# Hardware_v3.net
KiCad netlist of a schematic drawn in EAGLE
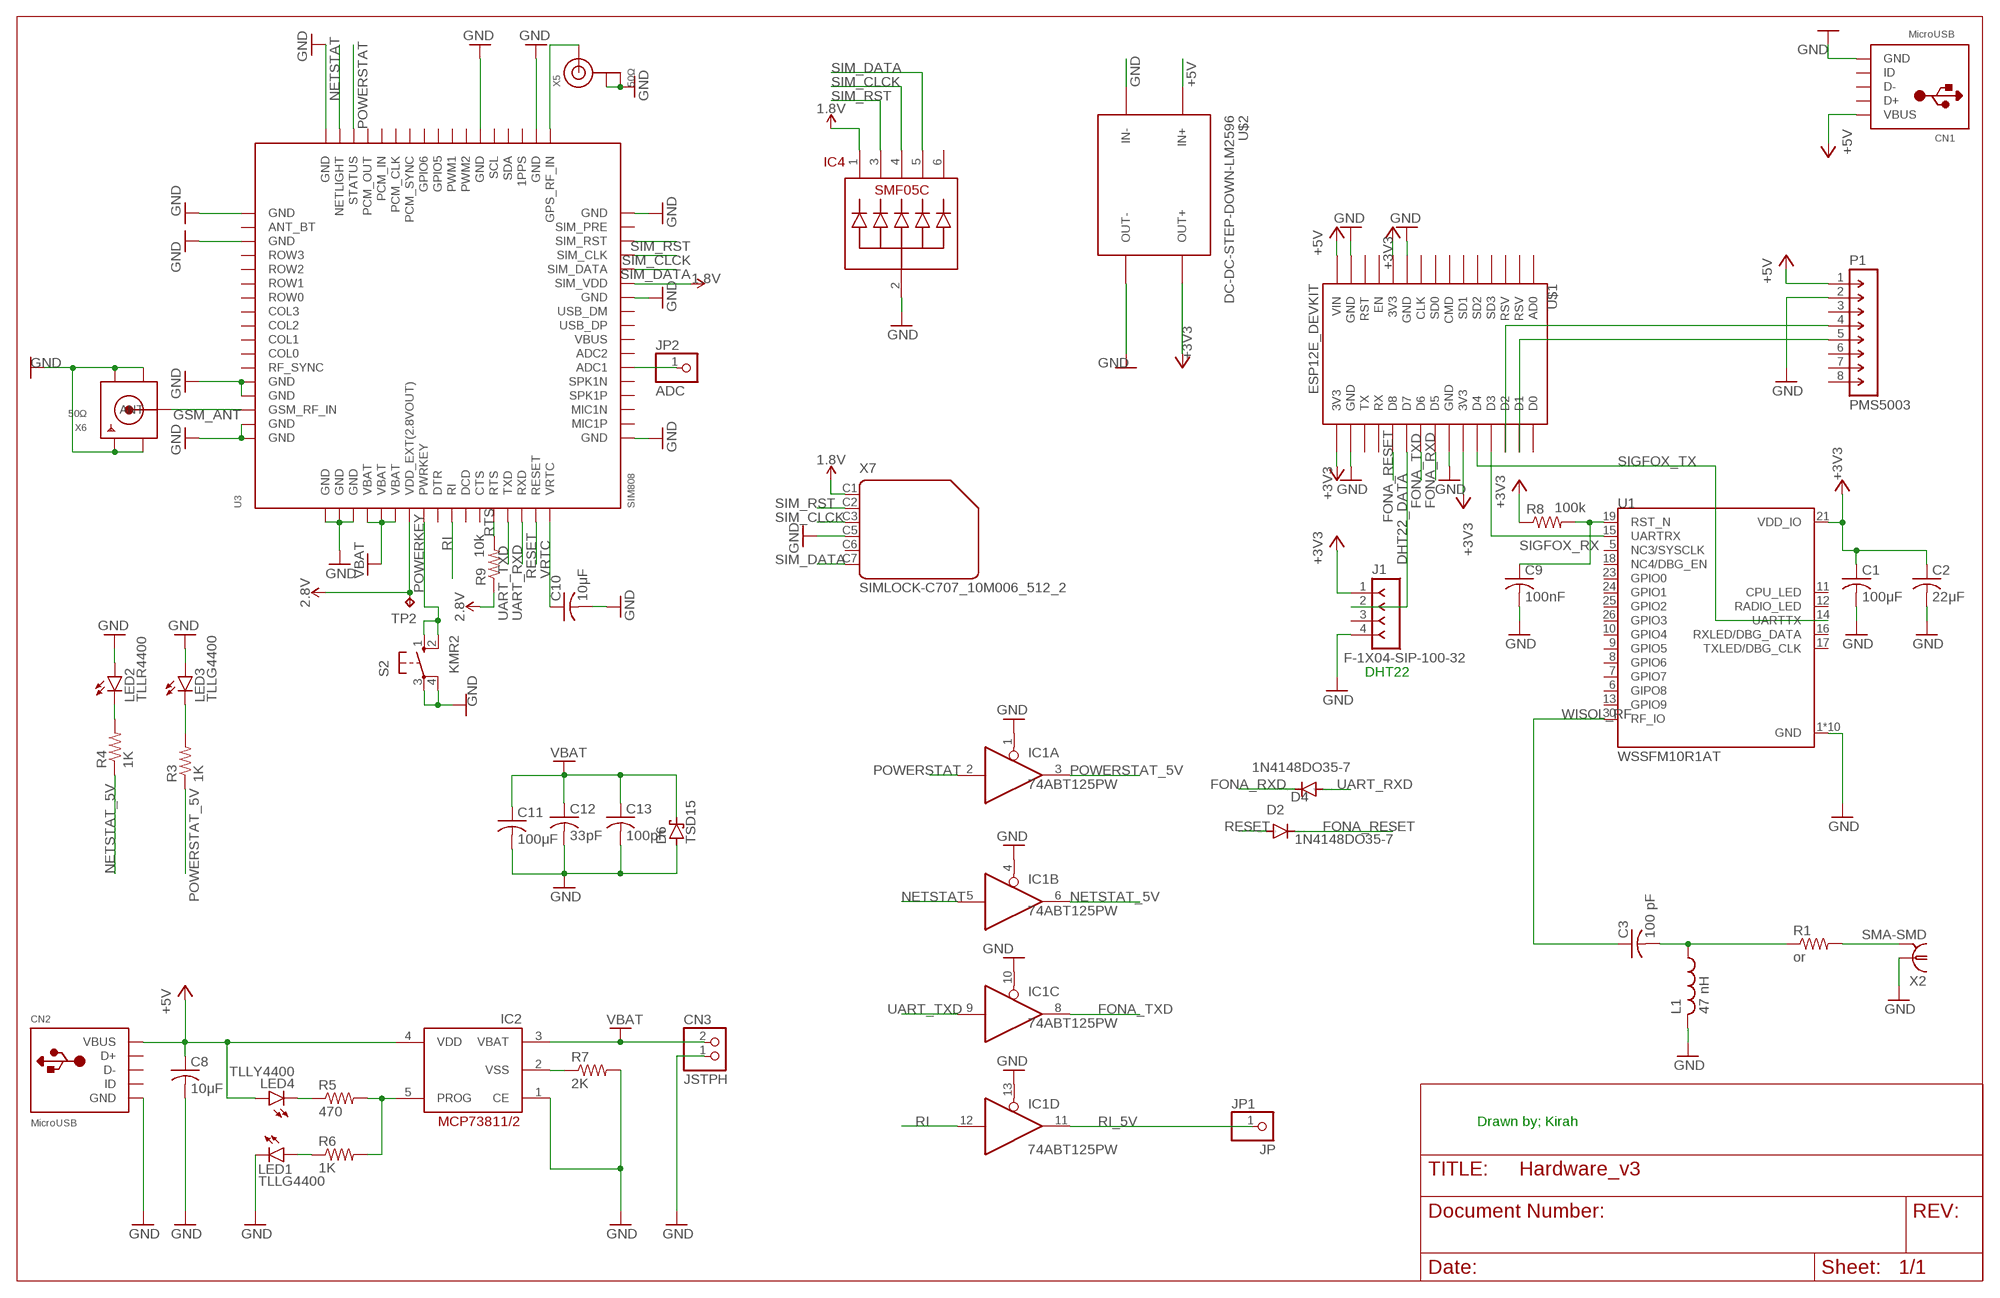
[diagram p0: schematic, sheet 1]

(export (version "E")
  (design (tool "Eeschema 10.0.6"))
  (components
    (comp (ref "C1")
      (value "100μF")
      (footprint "eagle-import:C0201")
      (libsource (lib "eagle-import") (part "C-USC0201"))
    )
    (comp (ref "C2")
      (value "22μF")
      (footprint "eagle-import:C0201")
      (libsource (lib "eagle-import") (part "C-USC0201"))
    )
    (comp (ref "C3")
      (value "100 pF")
      (footprint "eagle-import:C0201")
      (libsource (lib "eagle-import") (part "C-USC0201"))
    )
    (comp (ref "C8")
      (value "10μF")
      (footprint "eagle-import:C025-025X050")
      (libsource (lib "eagle-import") (part "C-US025-025X050"))
    )
    (comp (ref "C9")
      (value "100nF")
      (footprint "eagle-import:C025-025X050")
      (libsource (lib "eagle-import") (part "rcl_C-US025-025X050"))
    )
    (comp (ref "C10")
      (value "10μF")
      (footprint "eagle-import:C0402")
      (libsource (lib "eagle-import") (part "rcl_C-USC0402"))
    )
    (comp (ref "C11")
      (value "100μF")
      (footprint "eagle-import:C0402")
      (libsource (lib "eagle-import") (part "rcl_C-USC0402"))
    )
    (comp (ref "C12")
      (value "33pF")
      (footprint "eagle-import:C0402")
      (libsource (lib "eagle-import") (part "rcl_C-USC0402"))
    )
    (comp (ref "C13")
      (value "100pF")
      (footprint "eagle-import:C0402")
      (libsource (lib "eagle-import") (part "rcl_C-USC0402"))
    )
    (comp (ref "CN1")
      (value "MicroUSB")
      (footprint "eagle-import:USB-MINIB")
      (libsource (lib "eagle-import") (part "USBMINIB"))
    )
    (comp (ref "CN2")
      (value "MicroUSB")
      (footprint "eagle-import:USB-MINIB")
      (libsource (lib "eagle-import") (part "adafruit@1_USBMINIB"))
    )
    (comp (ref "CN3")
      (value "JSTPH")
      (footprint "eagle-import:JST-PH-2-SMT")
      (libsource (lib "eagle-import") (part "JST_2PIN-SMT"))
    )
    (comp (ref "D2")
      (value "1N4148DO35-7")
      (footprint "eagle-import:DO35-7")
      (libsource (lib "eagle-import") (part "1N4148DO35-7"))
    )
    (comp (ref "D4")
      (value "1N4148DO35-7")
      (footprint "eagle-import:DO35-7")
      (libsource (lib "eagle-import") (part "1N4148DO35-7"))
    )
    (comp (ref "D6")
      (value "TSD15")
      (footprint "eagle-import:CB429-15")
      (libsource (lib "eagle-import") (part "TSD15"))
    )
    (comp (ref "IC1")
      (value "74ABT125PW")
      (footprint "eagle-import:TSSOP14")
      (libsource (lib "eagle-import") (part "74125PWABT"))
    )
    (comp (ref "IC2")
      (value "MCP73811/2")
      (footprint "eagle-import:SOT23-5L")
      (libsource (lib "eagle-import") (part "MCP73811/2"))
    )
    (comp (ref "IC4")
      (value "SMF05C")
      (footprint "eagle-import:SC-70-6")
      (libsource (lib "eagle-import") (part "SMF05C"))
    )
    (comp (ref "J1")
      (value "F-1X04-SIP-100-32")
      (footprint "eagle-import:SIP-100-04-32")
      (libsource (lib "eagle-import") (part "F-1X04-SIP-100-32"))
    )
    (comp (ref "JP1")
      (value "JP")
      (footprint "eagle-import:1X01-CLEANBIG")
      (libsource (lib "eagle-import") (part "PINHD-1X1CB"))
    )
    (comp (ref "JP2")
      (value "ADC")
      (footprint "eagle-import:1X01M")
      (libsource (lib "eagle-import") (part "PINHD-1X01_2.00"))
    )
    (comp (ref "L1")
      (value "47 nH")
      (footprint "eagle-import:0204_7")
      (libsource (lib "eagle-import") (part "L-US0204/7"))
    )
    (comp (ref "LED1")
      (value "TLLG4400")
      (footprint "eagle-import:LED3MM")
      (fields (field (name "MF") "VISHAY SEMICONDUCTOR"))
      (libsource (lib "eagle-import") (part "TLLG4400"))
    )
    (comp (ref "LED2")
      (value "TLLR4400")
      (footprint "eagle-import:LED3MM")
      (fields (field (name "MF") "VISHAY SEMICONDUCTOR"))
      (libsource (lib "eagle-import") (part "TLLR4400"))
    )
    (comp (ref "LED3")
      (value "TLLG4400")
      (footprint "eagle-import:LED3MM")
      (fields (field (name "MF") "VISHAY SEMICONDUCTOR"))
      (libsource (lib "eagle-import") (part "TLLG4400"))
    )
    (comp (ref "LED4")
      (value "TLLY4400")
      (footprint "eagle-import:LED3MM")
      (fields (field (name "MF") "VISHAY SEMICONDUCTOR"))
      (libsource (lib "eagle-import") (part "TLLY4400"))
    )
    (comp (ref "P1")
      (value "PMS5003")
      (footprint "eagle-import:SIP-100-08-40")
      (libsource (lib "eagle-import") (part "M-1X08-SIP-100-40"))
    )
    (comp (ref "R1")
      (value "or")
      (footprint "eagle-import:0204_5")
      (libsource (lib "eagle-import") (part "R-US_0204/5"))
    )
    (comp (ref "R3")
      (value "1K")
      (footprint "eagle-import:0204_5")
      (libsource (lib "eagle-import") (part "R-US_0204/5"))
    )
    (comp (ref "R4")
      (value "1K")
      (footprint "eagle-import:0204_5")
      (libsource (lib "eagle-import") (part "R-US_0204/5"))
    )
    (comp (ref "R5")
      (value "470")
      (footprint "eagle-import:0204_5")
      (libsource (lib "eagle-import") (part "R-US_0204/5"))
    )
    (comp (ref "R6")
      (value "1K")
      (footprint "eagle-import:0204_5")
      (libsource (lib "eagle-import") (part "R-US_0204/5"))
    )
    (comp (ref "R7")
      (value "2K")
      (footprint "eagle-import:0204_5")
      (libsource (lib "eagle-import") (part "R-US_0204/5"))
    )
    (comp (ref "R8")
      (value "100k")
      (footprint "eagle-import:0204_7")
      (libsource (lib "eagle-import") (part "R-US_0204/7"))
    )
    (comp (ref "R9")
      (value "10k")
      (footprint "eagle-import:0204_5")
      (libsource (lib "eagle-import") (part "R-US_0204/5"))
    )
    (comp (ref "S2")
      (value "KMR2")
      (footprint "eagle-import:B3F_40XX")
      (libsource (lib "eagle-import") (part "40/XX"))
    )
    (comp (ref "TP2")
      (value "TPTP10R")
      (footprint "eagle-import:TP10R")
      (libsource (lib "eagle-import") (part "TPTP10R"))
    )
    (comp (ref "U$1")
      (value "ESP12E_DEVKIT")
      (footprint "eagle-import:ESP12E_DEVKIT")
      (libsource (lib "eagle-import") (part "ESP12E_DEVKIT"))
    )
    (comp (ref "U$2")
      (value "DC-DC-STEP-DOWN-LM2596")
      (footprint "eagle-import:DC-DC-STEP-DOWN-LM2596")
      (libsource (lib "eagle-import") (part "DC-DC-STEP-DOWN-LM2596"))
    )
    (comp (ref "U1")
      (value "WSSFM10R1AT")
      (footprint "eagle-import:XCVR_WSSFM10R1AT")
      (fields (field (name "MF") "Avnet Design Services"))
      (libsource (lib "eagle-import") (part "WSSFM10R1AT"))
    )
    (comp (ref "U3")
      (value "SIM808")
      (footprint "eagle-import:SIM900_SMT")
      (libsource (lib "eagle-import") (part "GSM_SIM808_LITERAL"))
    )
    (comp (ref "X2")
      (value "SMA-SMD")
      (footprint "eagle-import:SMA-SMD")
      (libsource (lib "eagle-import") (part "SMA-SMD"))
    )
    (comp (ref "X5")
      (value "50Ω")
      (footprint "eagle-import:U.FL")
      (libsource (lib "eagle-import") (part "ANTENNA_U.FL"))
    )
    (comp (ref "X6")
      (value "50Ω")
      (footprint "eagle-import:SMA_EDGELAUNCH_UFL")
      (libsource (lib "eagle-import") (part "SMACONNECTOR_EDGE_UFL"))
    )
    (comp (ref "X7")
      (value "SIMLOCK-C707_10M006_512_2")
      (footprint "eagle-import:C707_10M006_512_2")
      (libsource (lib "eagle-import") (part "SIMLOCK-C707_10M006_512_2"))
    )
  )
  (nets
    (net (code "1") (name "+3V3") (class "Default")
      (node (ref "C1") (pin "1") (pinfunction "1_1") (pintype "passive"))
      (node (ref "C2") (pin "1") (pinfunction "1_1") (pintype "passive"))
      (node (ref "J1") (pin "1") (pinfunction "1_1") (pintype "passive"))
      (node (ref "R8") (pin "1") (pinfunction "1_1") (pintype "passive"))
      (node (ref "U$1") (pin "3V3@0") (pinfunction "3V3_3V3@0") (pintype "bidirectional"))
      (node (ref "U$1") (pin "3V3@1") (pinfunction "3V3_3V3@1") (pintype "bidirectional"))
      (node (ref "U$1") (pin "3V3@2") (pinfunction "3V3_3V3@2") (pintype "bidirectional"))
      (node (ref "U$2") (pin "OUT+") (pinfunction "OUT+_OUT+") (pintype "bidirectional"))
      (node (ref "U1") (pin "21") (pinfunction "VDD_IO_21") (pintype "power_in"))
    )
    (net (code "2") (name "+5V") (class "Default")
      (node (ref "C8") (pin "1") (pinfunction "1_1") (pintype "passive"))
      (node (ref "CN1") (pin "VBUS") (pinfunction "VBUS_VBUS") (pintype "power_in"))
      (node (ref "CN2") (pin "VBUS") (pinfunction "VBUS_VBUS") (pintype "power_in"))
      (node (ref "IC2") (pin "4") (pinfunction "VDD_4") (pintype "power_in"))
      (node (ref "LED4") (pin "A") (pinfunction "A_A") (pintype "passive"))
      (node (ref "P1") (pin "1") (pinfunction "1_1") (pintype "passive"))
      (node (ref "U$1") (pin "VIN") (pinfunction "VIN_VIN") (pintype "bidirectional"))
      (node (ref "U$2") (pin "IN+") (pinfunction "IN+_IN+") (pintype "bidirectional"))
    )
    (net (code "3") (name "/DHT22_DATA") (class "Default")
      (node (ref "J1") (pin "2") (pinfunction "2_2") (pintype "passive"))
      (node (ref "U$1") (pin "D7") (pinfunction "D7_D7") (pintype "bidirectional"))
    )
    (net (code "4") (name "/FONA_RESET") (class "Default")
      (node (ref "D2") (pin "C") (pinfunction "C_C") (pintype "passive"))
      (node (ref "U$1") (pin "D8") (pinfunction "D8_D8") (pintype "bidirectional"))
    )
    (net (code "5") (name "/FONA_RXD") (class "Default")
      (node (ref "D4") (pin "C") (pinfunction "C_C") (pintype "passive"))
      (node (ref "U$1") (pin "D5") (pinfunction "D5_D5") (pintype "bidirectional"))
    )
    (net (code "6") (name "/FONA_TXD") (class "Default")
      (node (ref "IC1") (pin "8") (pinfunction "O_8") (pintype "tri_state"))
      (node (ref "U$1") (pin "D6") (pinfunction "D6_D6") (pintype "bidirectional"))
    )
    (net (code "7") (name "/GSM_ANT") (class "Default")
      (node (ref "U3") (pin "P$66") (pinfunction "GSM_RF_IN_P$66") (pintype "input"))
      (node (ref "X6") (pin "P") (pinfunction "ANT_P") (pintype "bidirectional"))
    )
    (net (code "8") (name "/NETSTAT") (class "Default")
      (node (ref "IC1") (pin "5") (pinfunction "I_5") (pintype "input"))
      (node (ref "U3") (pin "P$50") (pinfunction "NETLIGHT_P$50") (pintype "output"))
    )
    (net (code "9") (name "/NETSTAT_5V") (class "Default")
      (node (ref "IC1") (pin "6") (pinfunction "O_6") (pintype "tri_state"))
      (node (ref "R4") (pin "1") (pinfunction "1_1") (pintype "passive"))
    )
    (net (code "10") (name "/POWERKEY") (class "Default")
      (node (ref "S2") (pin "1") (pinfunction "S_1") (pintype "passive"))
      (node (ref "S2") (pin "2") (pinfunction "S1_2") (pintype "passive"))
      (node (ref "U3") (pin "P$8") (pinfunction "PWRKEY_P$8") (pintype "input"))
    )
    (net (code "11") (name "/POWERSTAT") (class "Default")
      (node (ref "IC1") (pin "2") (pinfunction "I_2") (pintype "input"))
      (node (ref "U3") (pin "P$49") (pinfunction "STATUS_P$49") (pintype "output"))
    )
    (net (code "12") (name "/POWERSTAT_5V") (class "Default")
      (node (ref "IC1") (pin "3") (pinfunction "O_3") (pintype "tri_state"))
      (node (ref "R3") (pin "1") (pinfunction "1_1") (pintype "passive"))
    )
    (net (code "13") (name "/RESET") (class "Default")
      (node (ref "D2") (pin "A") (pinfunction "A_A") (pintype "passive"))
      (node (ref "U3") (pin "P$16") (pinfunction "RESET_P$16") (pintype "input"))
    )
    (net (code "14") (name "/RI") (class "Default")
      (node (ref "IC1") (pin "12") (pinfunction "I_12") (pintype "input"))
      (node (ref "U3") (pin "P$10") (pinfunction "RI_P$10") (pintype "output"))
    )
    (net (code "15") (name "/RI_5V") (class "Default")
      (node (ref "IC1") (pin "11") (pinfunction "O_11") (pintype "tri_state"))
      (node (ref "JP1") (pin "1") (pinfunction "1_1") (pintype "passive"))
    )
    (net (code "16") (name "/RTS") (class "Default")
      (node (ref "R9") (pin "2") (pinfunction "2_2") (pintype "passive"))
      (node (ref "U3") (pin "P$13") (pinfunction "RTS_P$13") (pintype "input"))
    )
    (net (code "17") (name "/SIGFOX_RX") (class "Default")
      (node (ref "U$1") (pin "D3") (pinfunction "D3_D3") (pintype "bidirectional"))
      (node (ref "U1") (pin "15") (pinfunction "UARTRX_15") (pintype "input"))
    )
    (net (code "18") (name "/SIGFOX_TX") (class "Default")
      (node (ref "U$1") (pin "D4") (pinfunction "D4_D4") (pintype "bidirectional"))
      (node (ref "U1") (pin "14") (pinfunction "UARTTX_14") (pintype "output"))
    )
    (net (code "19") (name "/SIM_CLCK") (class "Default")
      (node (ref "IC4") (pin "4") (pinfunction "4_4") (pintype "bidirectional"))
      (node (ref "U3") (pin "P$31") (pinfunction "SIM_CLK_P$31") (pintype "output"))
      (node (ref "X7") (pin "C3") (pinfunction "3_C3") (pintype "passive"))
    )
    (net (code "20") (name "/SIM_DATA") (class "Default")
      (node (ref "IC4") (pin "5") (pinfunction "5_5") (pintype "bidirectional"))
      (node (ref "U3") (pin "P$30") (pinfunction "SIM_DATA_P$30") (pintype "bidirectional"))
      (node (ref "X7") (pin "C7") (pinfunction "6_C7") (pintype "passive"))
    )
    (net (code "21") (name "/SIM_RST") (class "Default")
      (node (ref "IC4") (pin "3") (pinfunction "3_3") (pintype "bidirectional"))
      (node (ref "U3") (pin "P$32") (pinfunction "SIM_RST_P$32") (pintype "output"))
      (node (ref "X7") (pin "C2") (pinfunction "2_C2") (pintype "passive"))
    )
    (net (code "22") (name "/UART_RXD") (class "Default")
      (node (ref "D4") (pin "A") (pinfunction "A_A") (pintype "passive"))
      (node (ref "U3") (pin "P$15") (pinfunction "RXD_P$15") (pintype "input"))
    )
    (net (code "23") (name "/UART_TXD") (class "Default")
      (node (ref "IC1") (pin "9") (pinfunction "I_9") (pintype "input"))
      (node (ref "U3") (pin "P$14") (pinfunction "TXD_P$14") (pintype "output"))
    )
    (net (code "24") (name "/VBUS") (class "Default")
      (node (ref "U3") (pin "P$25") (pinfunction "VBUS_P$25") (pintype "power_in"))
    )
    (net (code "25") (name "/VRTC") (class "Default")
      (node (ref "C10") (pin "1") (pinfunction "1_1") (pintype "passive"))
      (node (ref "U3") (pin "P$17") (pinfunction "VRTC_P$17") (pintype "power_in"))
    )
    (net (code "26") (name "/WISOL_RF") (class "Default")
      (node (ref "C3") (pin "1") (pinfunction "1_1") (pintype "passive"))
      (node (ref "U1") (pin "30") (pinfunction "RF_IO_30") (pintype "bidirectional"))
    )
    (net (code "27") (name "1.8V") (class "Default")
      (node (ref "IC4") (pin "1") (pinfunction "1_1") (pintype "bidirectional"))
      (node (ref "U3") (pin "P$29") (pinfunction "SIM_VDD_P$29") (pintype "power_in"))
      (node (ref "X7") (pin "C1") (pinfunction "1_C1") (pintype "passive"))
    )
    (net (code "28") (name "2.8V") (class "Default")
      (node (ref "R9") (pin "1") (pinfunction "1_1") (pintype "passive"))
      (node (ref "TP2") (pin "TP") (pinfunction "TP_TP") (pintype "input"))
      (node (ref "U3") (pin "P$7") (pinfunction "VDD_EXT(2.8VOUT)_P$7") (pintype "power_in"))
    )
    (net (code "29") (name "GND") (class "Default")
      (node (ref "C1") (pin "2") (pinfunction "2_2") (pintype "passive"))
      (node (ref "C10") (pin "2") (pinfunction "2_2") (pintype "passive"))
      (node (ref "C11") (pin "2") (pinfunction "2_2") (pintype "passive"))
      (node (ref "C12") (pin "2") (pinfunction "2_2") (pintype "passive"))
      (node (ref "C13") (pin "2") (pinfunction "2_2") (pintype "passive"))
      (node (ref "C2") (pin "2") (pinfunction "2_2") (pintype "passive"))
      (node (ref "C8") (pin "2") (pinfunction "2_2") (pintype "passive"))
      (node (ref "C9") (pin "2") (pinfunction "2_2") (pintype "passive"))
      (node (ref "CN1") (pin "GND") (pinfunction "GND_GND") (pintype "power_in"))
      (node (ref "CN2") (pin "GND") (pinfunction "GND_GND") (pintype "power_in"))
      (node (ref "CN3") (pin "1") (pinfunction "2_1") (pintype "passive"))
      (node (ref "D6") (pin "A") (pinfunction "A_A") (pintype "passive"))
      (node (ref "IC1") (pin "1") (pinfunction "OE_1") (pintype "input"))
      (node (ref "IC1") (pin "10") (pinfunction "OE_10") (pintype "input"))
      (node (ref "IC1") (pin "13") (pinfunction "OE_13") (pintype "input"))
      (node (ref "IC1") (pin "4") (pinfunction "OE_4") (pintype "input"))
      (node (ref "IC2") (pin "1") (pinfunction "CE_1") (pintype "input"))
      (node (ref "IC4") (pin "2") (pinfunction "2_2") (pintype "bidirectional"))
      (node (ref "J1") (pin "4") (pinfunction "4_4") (pintype "passive"))
      (node (ref "L1") (pin "2") (pinfunction "2_2") (pintype "passive"))
      (node (ref "LED1") (pin "K") (pinfunction "C_K") (pintype "passive"))
      (node (ref "LED2") (pin "A") (pinfunction "A_A") (pintype "passive"))
      (node (ref "LED3") (pin "A") (pinfunction "A_A") (pintype "passive"))
      (node (ref "P1") (pin "2") (pinfunction "2_2") (pintype "passive"))
      (node (ref "R7") (pin "2") (pinfunction "2_2") (pintype "passive"))
      (node (ref "S2") (pin "3") (pinfunction "P_3") (pintype "passive"))
      (node (ref "S2") (pin "4") (pinfunction "P1_4") (pintype "passive"))
      (node (ref "U$1") (pin "GND@0") (pinfunction "GND_GND@0") (pintype "bidirectional"))
      (node (ref "U$1") (pin "GND@1") (pinfunction "GND_GND@1") (pintype "bidirectional"))
      (node (ref "U$1") (pin "GND@2") (pinfunction "GND_GND@2") (pintype "bidirectional"))
      (node (ref "U$1") (pin "GND@3") (pinfunction "GND_GND@3") (pintype "bidirectional"))
      (node (ref "U$2") (pin "IN-") (pinfunction "IN-_IN-") (pintype "bidirectional"))
      (node (ref "U$2") (pin "OUT-") (pinfunction "OUT-_OUT-") (pintype "bidirectional"))
      (node (ref "U1") (pin "1") (pinfunction "GND_1") (pintype "power_in"))
      (node (ref "U1") (pin "2") (pinfunction "GND_2") (pintype "power_in"))
      (node (ref "U1") (pin "20") (pinfunction "GND_20") (pintype "power_in"))
      (node (ref "U1") (pin "22") (pinfunction "GND_22") (pintype "power_in"))
      (node (ref "U1") (pin "27") (pinfunction "GND_27") (pintype "power_in"))
      (node (ref "U1") (pin "28") (pinfunction "GND_28") (pintype "power_in"))
      (node (ref "U1") (pin "29") (pinfunction "GND_29") (pintype "power_in"))
      (node (ref "U1") (pin "3") (pinfunction "GND_3") (pintype "power_in"))
      (node (ref "U1") (pin "31") (pinfunction "GND_31") (pintype "power_in"))
      (node (ref "U1") (pin "4") (pinfunction "GND_4") (pintype "power_in"))
      (node (ref "U3") (pin "P$1") (pinfunction "GND_P$1") (pintype "power_in"))
      (node (ref "U3") (pin "P$18") (pinfunction "GND_P$18") (pintype "power_in"))
      (node (ref "U3") (pin "P$2") (pinfunction "GND_P$2") (pintype "power_in"))
      (node (ref "U3") (pin "P$28") (pinfunction "GND_P$28") (pintype "power_in"))
      (node (ref "U3") (pin "P$3") (pinfunction "GND_P$3") (pintype "power_in"))
      (node (ref "U3") (pin "P$34") (pinfunction "GND_P$34") (pintype "power_in"))
      (node (ref "U3") (pin "P$36") (pinfunction "GND_P$36") (pintype "power_in"))
      (node (ref "U3") (pin "P$40") (pinfunction "GND_P$40") (pintype "power_in"))
      (node (ref "U3") (pin "P$51") (pinfunction "GND_P$51") (pintype "power_in"))
      (node (ref "U3") (pin "P$52") (pinfunction "GND_P$52") (pintype "power_in"))
      (node (ref "U3") (pin "P$54") (pinfunction "GND_P$54") (pintype "power_in"))
      (node (ref "U3") (pin "P$64") (pinfunction "GND_P$64") (pintype "power_in"))
      (node (ref "U3") (pin "P$65") (pinfunction "GND_P$65") (pintype "power_in"))
      (node (ref "U3") (pin "P$67") (pinfunction "GND_P$67") (pintype "power_in"))
      (node (ref "U3") (pin "P$68") (pinfunction "GND_P$68") (pintype "power_in"))
      (node (ref "X2") (pin "1") (pinfunction "1_1") (pintype "passive"))
      (node (ref "X5") (pin "1") (pinfunction "GND_1") (pintype "passive"))
      (node (ref "X5") (pin "2") (pinfunction "GND_2") (pintype "passive"))
      (node (ref "X6") (pin "GND@1") (pinfunction "GND1_GND@1") (pintype "power_in"))
      (node (ref "X6") (pin "GND@2") (pinfunction "GND2_GND@2") (pintype "power_in"))
      (node (ref "X6") (pin "GND@3") (pinfunction "GND3_GND@3") (pintype "power_in"))
      (node (ref "X6") (pin "GND@4") (pinfunction "GND4_GND@4") (pintype "power_in"))
      (node (ref "X7") (pin "C5") (pinfunction "4_C5") (pintype "passive"))
    )
    (net (code "30") (name "Net-(C3-Pad2)") (class "Default")
      (node (ref "C3") (pin "2") (pinfunction "2_2") (pintype "passive"))
      (node (ref "L1") (pin "1") (pinfunction "1_1") (pintype "passive"))
      (node (ref "R1") (pin "1") (pinfunction "1_1") (pintype "passive"))
    )
    (net (code "31") (name "Net-(IC2-PROG)") (class "Default")
      (node (ref "IC2") (pin "5") (pinfunction "PROG_5") (pintype "input"))
      (node (ref "R5") (pin "2") (pinfunction "2_2") (pintype "passive"))
      (node (ref "R6") (pin "2") (pinfunction "2_2") (pintype "passive"))
    )
    (net (code "32") (name "Net-(IC2-VSS)") (class "Default")
      (node (ref "IC2") (pin "2") (pinfunction "VSS_2") (pintype "power_in"))
      (node (ref "R7") (pin "1") (pinfunction "1_1") (pintype "passive"))
    )
    (net (code "33") (name "Net-(LED1-PadA)") (class "Default")
      (node (ref "LED1") (pin "A") (pinfunction "A_A") (pintype "passive"))
      (node (ref "R6") (pin "1") (pinfunction "1_1") (pintype "passive"))
    )
    (net (code "34") (name "Net-(LED2-C)") (class "Default")
      (node (ref "LED2") (pin "K") (pinfunction "C_K") (pintype "passive"))
      (node (ref "R4") (pin "2") (pinfunction "2_2") (pintype "passive"))
    )
    (net (code "35") (name "Net-(LED3-C)") (class "Default")
      (node (ref "LED3") (pin "K") (pinfunction "C_K") (pintype "passive"))
      (node (ref "R3") (pin "2") (pinfunction "2_2") (pintype "passive"))
    )
    (net (code "36") (name "Net-(LED4-C)") (class "Default")
      (node (ref "LED4") (pin "K") (pinfunction "C_K") (pintype "passive"))
      (node (ref "R5") (pin "1") (pinfunction "1_1") (pintype "passive"))
    )
    (net (code "37") (name "Net-(P1-Pad4)") (class "Default")
      (node (ref "P1") (pin "4") (pinfunction "4_4") (pintype "passive"))
      (node (ref "U$1") (pin "D2") (pinfunction "D2_D2") (pintype "bidirectional"))
    )
    (net (code "38") (name "Net-(P1-Pad5)") (class "Default")
      (node (ref "P1") (pin "5") (pinfunction "5_5") (pintype "passive"))
      (node (ref "U$1") (pin "D1") (pinfunction "D1_D1") (pintype "bidirectional"))
    )
    (net (code "39") (name "Net-(R1-Pad2)") (class "Default")
      (node (ref "R1") (pin "2") (pinfunction "2_2") (pintype "passive"))
      (node (ref "X2") (pin "2@1") (pinfunction "2_2@1") (pintype "passive"))
      (node (ref "X2") (pin "2@2") (pinfunction "2_2@2") (pintype "passive"))
      (node (ref "X2") (pin "2@3") (pinfunction "2_2@3") (pintype "passive"))
      (node (ref "X2") (pin "2@4") (pinfunction "2_2@4") (pintype "passive"))
      (node (ref "X2") (pin "2@5") (pinfunction "2_2@5") (pintype "passive"))
      (node (ref "X2") (pin "2@6") (pinfunction "2_2@6") (pintype "passive"))
    )
    (net (code "40") (name "Net-(U1-RST_N)") (class "Default")
      (node (ref "C9") (pin "1") (pinfunction "1_1") (pintype "passive"))
      (node (ref "R8") (pin "2") (pinfunction "2_2") (pintype "passive"))
      (node (ref "U1") (pin "19") (pinfunction "RST_N_19") (pintype "input"))
    )
    (net (code "41") (name "Net-(U3-ADC1)") (class "Default")
      (node (ref "JP2") (pin "1") (pinfunction "1_1") (pintype "passive"))
      (node (ref "U3") (pin "P$23") (pinfunction "ADC1_P$23") (pintype "input"))
    )
    (net (code "42") (name "Net-(U3-GPS_RF_IN)") (class "Default")
      (node (ref "U3") (pin "P$35") (pinfunction "GPS_RF_IN_P$35") (pintype "bidirectional"))
      (node (ref "X5") (pin "3") (pinfunction "SIGNAL_3") (pintype "passive"))
    )
    (net (code "43") (name "VBAT") (class "Default")
      (node (ref "C11") (pin "1") (pinfunction "1_1") (pintype "passive"))
      (node (ref "C12") (pin "1") (pinfunction "1_1") (pintype "passive"))
      (node (ref "C13") (pin "1") (pinfunction "1_1") (pintype "passive"))
      (node (ref "CN3") (pin "2") (pinfunction "1_2") (pintype "passive"))
      (node (ref "D6") (pin "C") (pinfunction "C_C") (pintype "passive"))
      (node (ref "IC2") (pin "3") (pinfunction "VBAT_3") (pintype "bidirectional"))
      (node (ref "U3") (pin "P$4") (pinfunction "VBAT_P$4") (pintype "power_in"))
      (node (ref "U3") (pin "P$5") (pinfunction "VBAT_P$5") (pintype "power_in"))
      (node (ref "U3") (pin "P$6") (pinfunction "VBAT_P$6") (pintype "power_in"))
    )
    (net (code "44") (name "unconnected-(CN1-PadD+)") (class "Default")
      (node (ref "CN1") (pin "D+") (pinfunction "D+_D+") (pintype "bidirectional"))
    )
    (net (code "45") (name "unconnected-(CN1-PadD-)") (class "Default")
      (node (ref "CN1") (pin "D-") (pinfunction "D-_D-") (pintype "bidirectional"))
    )
    (net (code "46") (name "unconnected-(CN1-PadID)") (class "Default")
      (node (ref "CN1") (pin "ID") (pinfunction "ID_ID") (pintype "bidirectional"))
    )
    (net (code "47") (name "unconnected-(CN2-PadD+)") (class "Default")
      (node (ref "CN2") (pin "D+") (pinfunction "D+_D+") (pintype "bidirectional"))
    )
    (net (code "48") (name "unconnected-(CN2-PadD-)") (class "Default")
      (node (ref "CN2") (pin "D-") (pinfunction "D-_D-") (pintype "bidirectional"))
    )
    (net (code "49") (name "unconnected-(CN2-PadID)") (class "Default")
      (node (ref "CN2") (pin "ID") (pinfunction "ID_ID") (pintype "bidirectional"))
    )
    (net (code "50") (name "unconnected-(IC4-Pad6)") (class "Default")
      (node (ref "IC4") (pin "6") (pinfunction "6_6") (pintype "bidirectional"))
    )
    (net (code "51") (name "unconnected-(J1-Pad3)") (class "Default")
      (node (ref "J1") (pin "3") (pinfunction "3_3") (pintype "passive"))
    )
    (net (code "52") (name "unconnected-(P1-Pad3)") (class "Default")
      (node (ref "P1") (pin "3") (pinfunction "3_3") (pintype "passive"))
    )
    (net (code "53") (name "unconnected-(P1-Pad6)") (class "Default")
      (node (ref "P1") (pin "6") (pinfunction "6_6") (pintype "passive"))
    )
    (net (code "54") (name "unconnected-(P1-Pad7)") (class "Default")
      (node (ref "P1") (pin "7") (pinfunction "7_7") (pintype "passive"))
    )
    (net (code "55") (name "unconnected-(P1-Pad8)") (class "Default")
      (node (ref "P1") (pin "8") (pinfunction "8_8") (pintype "passive"))
    )
    (net (code "56") (name "unconnected-(U$1-PadAD0)") (class "Default")
      (node (ref "U$1") (pin "AD0") (pinfunction "AD0_AD0") (pintype "bidirectional"))
    )
    (net (code "57") (name "unconnected-(U$1-PadCLK)") (class "Default")
      (node (ref "U$1") (pin "CLK") (pinfunction "CLK_CLK") (pintype "bidirectional"))
    )
    (net (code "58") (name "unconnected-(U$1-PadCMD)") (class "Default")
      (node (ref "U$1") (pin "CMD") (pinfunction "CMD_CMD") (pintype "bidirectional"))
    )
    (net (code "59") (name "unconnected-(U$1-PadD0)") (class "Default")
      (node (ref "U$1") (pin "D0") (pinfunction "D0_D0") (pintype "bidirectional"))
    )
    (net (code "60") (name "unconnected-(U$1-PadEN)") (class "Default")
      (node (ref "U$1") (pin "EN") (pinfunction "EN_EN") (pintype "bidirectional"))
    )
    (net (code "61") (name "unconnected-(U$1-PadRST)") (class "Default")
      (node (ref "U$1") (pin "RST") (pinfunction "RST_RST") (pintype "bidirectional"))
    )
    (net (code "62") (name "unconnected-(U$1-PadRX)") (class "Default")
      (node (ref "U$1") (pin "RX") (pinfunction "RX_RX") (pintype "bidirectional"))
    )
    (net (code "63") (name "unconnected-(U$1-PadSD0)") (class "Default")
      (node (ref "U$1") (pin "SD0") (pinfunction "SD0_SD0") (pintype "bidirectional"))
    )
    (net (code "64") (name "unconnected-(U$1-PadSD1)") (class "Default")
      (node (ref "U$1") (pin "SD1") (pinfunction "SD1_SD1") (pintype "bidirectional"))
    )
    (net (code "65") (name "unconnected-(U$1-PadSD2)") (class "Default")
      (node (ref "U$1") (pin "SD2") (pinfunction "SD2_SD2") (pintype "bidirectional"))
    )
    (net (code "66") (name "unconnected-(U$1-PadSD3)") (class "Default")
      (node (ref "U$1") (pin "SD3") (pinfunction "SD3_SD3") (pintype "bidirectional"))
    )
    (net (code "67") (name "unconnected-(U$1-PadTX)") (class "Default")
      (node (ref "U$1") (pin "TX") (pinfunction "TX_TX") (pintype "bidirectional"))
    )
    (net (code "68") (name "unconnected-(U$1-RSV-PadRSV@0)") (class "Default")
      (node (ref "U$1") (pin "RSV@0") (pinfunction "RSV_RSV@0") (pintype "bidirectional"))
    )
    (net (code "69") (name "unconnected-(U$1-RSV-PadRSV@1)") (class "Default")
      (node (ref "U$1") (pin "RSV@1") (pinfunction "RSV_RSV@1") (pintype "bidirectional"))
    )
    (net (code "70") (name "unconnected-(U1-CPU_LED-Pad11)") (class "Default")
      (node (ref "U1") (pin "11") (pinfunction "CPU_LED_11") (pintype "output"))
    )
    (net (code "71") (name "unconnected-(U1-GIPO8-Pad6)") (class "Default")
      (node (ref "U1") (pin "6") (pinfunction "GIPO8_6") (pintype "bidirectional"))
    )
    (net (code "72") (name "unconnected-(U1-GPIO0-Pad23)") (class "Default")
      (node (ref "U1") (pin "23") (pinfunction "GPIO0_23") (pintype "bidirectional"))
    )
    (net (code "73") (name "unconnected-(U1-GPIO1-Pad24)") (class "Default")
      (node (ref "U1") (pin "24") (pinfunction "GPIO1_24") (pintype "bidirectional"))
    )
    (net (code "74") (name "unconnected-(U1-GPIO2-Pad25)") (class "Default")
      (node (ref "U1") (pin "25") (pinfunction "GPIO2_25") (pintype "bidirectional"))
    )
    (net (code "75") (name "unconnected-(U1-GPIO3-Pad26)") (class "Default")
      (node (ref "U1") (pin "26") (pinfunction "GPIO3_26") (pintype "bidirectional"))
    )
    (net (code "76") (name "unconnected-(U1-GPIO4-Pad10)") (class "Default")
      (node (ref "U1") (pin "10") (pinfunction "GPIO4_10") (pintype "input"))
    )
    (net (code "77") (name "unconnected-(U1-GPIO5-Pad9)") (class "Default")
      (node (ref "U1") (pin "9") (pinfunction "GPIO5_9") (pintype "bidirectional"))
    )
    (net (code "78") (name "unconnected-(U1-GPIO6-Pad8)") (class "Default")
      (node (ref "U1") (pin "8") (pinfunction "GPIO6_8") (pintype "bidirectional"))
    )
    (net (code "79") (name "unconnected-(U1-GPIO7-Pad7)") (class "Default")
      (node (ref "U1") (pin "7") (pinfunction "GPIO7_7") (pintype "bidirectional"))
    )
    (net (code "80") (name "unconnected-(U1-GPIO9-Pad13)") (class "Default")
      (node (ref "U1") (pin "13") (pinfunction "GPIO9_13") (pintype "input"))
    )
    (net (code "81") (name "unconnected-(U1-NC3{slash}SYSCLK-Pad5)") (class "Default")
      (node (ref "U1") (pin "5") (pinfunction "NC3/SYSCLK_5") (pintype "input"))
    )
    (net (code "82") (name "unconnected-(U1-NC4{slash}DBG_EN-Pad18)") (class "Default")
      (node (ref "U1") (pin "18") (pinfunction "NC4/DBG_EN_18") (pintype "input"))
    )
    (net (code "83") (name "unconnected-(U1-RADIO_LED-Pad12)") (class "Default")
      (node (ref "U1") (pin "12") (pinfunction "RADIO_LED_12") (pintype "output"))
    )
    (net (code "84") (name "unconnected-(U1-RXLED{slash}DBG_DATA-Pad16)") (class "Default")
      (node (ref "U1") (pin "16") (pinfunction "RXLED/DBG_DATA_16") (pintype "output"))
    )
    (net (code "85") (name "unconnected-(U1-TXLED{slash}DBG_CLK-Pad17)") (class "Default")
      (node (ref "U1") (pin "17") (pinfunction "TXLED/DBG_CLK_17") (pintype "output"))
    )
    (net (code "86") (name "unconnected-(U3-1PPS-PadP$37)") (class "Default")
      (node (ref "U3") (pin "P$37") (pinfunction "1PPS_P$37") (pintype "input"))
    )
    (net (code "87") (name "unconnected-(U3-ADC2-PadP$24)") (class "Default")
      (node (ref "U3") (pin "P$24") (pinfunction "ADC2_P$24") (pintype "input"))
    )
    (net (code "88") (name "unconnected-(U3-ANT_BT-PadP$53)") (class "Default")
      (node (ref "U3") (pin "P$53") (pinfunction "ANT_BT_P$53") (pintype "bidirectional"))
    )
    (net (code "89") (name "unconnected-(U3-COL0-PadP$62)") (class "Default")
      (node (ref "U3") (pin "P$62") (pinfunction "COL0_P$62") (pintype "input"))
    )
    (net (code "90") (name "unconnected-(U3-COL1-PadP$61)") (class "Default")
      (node (ref "U3") (pin "P$61") (pinfunction "COL1_P$61") (pintype "input"))
    )
    (net (code "91") (name "unconnected-(U3-COL2-PadP$60)") (class "Default")
      (node (ref "U3") (pin "P$60") (pinfunction "COL2_P$60") (pintype "input"))
    )
    (net (code "92") (name "unconnected-(U3-COL3-PadP$59)") (class "Default")
      (node (ref "U3") (pin "P$59") (pinfunction "COL3_P$59") (pintype "input"))
    )
    (net (code "93") (name "unconnected-(U3-CTS-PadP$12)") (class "Default")
      (node (ref "U3") (pin "P$12") (pinfunction "CTS_P$12") (pintype "output"))
    )
    (net (code "94") (name "unconnected-(U3-DCD-PadP$11)") (class "Default")
      (node (ref "U3") (pin "P$11") (pinfunction "DCD_P$11") (pintype "output"))
    )
    (net (code "95") (name "unconnected-(U3-DTR-PadP$9)") (class "Default")
      (node (ref "U3") (pin "P$9") (pinfunction "DTR_P$9") (pintype "input"))
    )
    (net (code "96") (name "unconnected-(U3-GPIO5-PadP$43)") (class "Default")
      (node (ref "U3") (pin "P$43") (pinfunction "GPIO5_P$43") (pintype "bidirectional"))
    )
    (net (code "97") (name "unconnected-(U3-GPIO6-PadP$44)") (class "Default")
      (node (ref "U3") (pin "P$44") (pinfunction "GPIO6_P$44") (pintype "bidirectional"))
    )
    (net (code "98") (name "unconnected-(U3-MIC1N-PadP$20)") (class "Default")
      (node (ref "U3") (pin "P$20") (pinfunction "MIC1N_P$20") (pintype "input"))
    )
    (net (code "99") (name "unconnected-(U3-MIC1P-PadP$19)") (class "Default")
      (node (ref "U3") (pin "P$19") (pinfunction "MIC1P_P$19") (pintype "input"))
    )
    (net (code "100") (name "unconnected-(U3-PCM_CLK-PadP$46)") (class "Default")
      (node (ref "U3") (pin "P$46") (pinfunction "PCM_CLK_P$46") (pintype "input"))
    )
    (net (code "101") (name "unconnected-(U3-PCM_IN-PadP$47)") (class "Default")
      (node (ref "U3") (pin "P$47") (pinfunction "PCM_IN_P$47") (pintype "input"))
    )
    (net (code "102") (name "unconnected-(U3-PCM_OUT-PadP$48)") (class "Default")
      (node (ref "U3") (pin "P$48") (pinfunction "PCM_OUT_P$48") (pintype "output"))
    )
    (net (code "103") (name "unconnected-(U3-PCM_SYNC-PadP$45)") (class "Default")
      (node (ref "U3") (pin "P$45") (pinfunction "PCM_SYNC_P$45") (pintype "output"))
    )
    (net (code "104") (name "unconnected-(U3-PWM1-PadP$42)") (class "Default")
      (node (ref "U3") (pin "P$42") (pinfunction "PWM1_P$42") (pintype "output"))
    )
    (net (code "105") (name "unconnected-(U3-PWM2-PadP$41)") (class "Default")
      (node (ref "U3") (pin "P$41") (pinfunction "PWM2_P$41") (pintype "output"))
    )
    (net (code "106") (name "unconnected-(U3-RF_SYNC-PadP$63)") (class "Default")
      (node (ref "U3") (pin "P$63") (pinfunction "RF_SYNC_P$63") (pintype "output"))
    )
    (net (code "107") (name "unconnected-(U3-ROW0-PadP$58)") (class "Default")
      (node (ref "U3") (pin "P$58") (pinfunction "ROW0_P$58") (pintype "output"))
    )
    (net (code "108") (name "unconnected-(U3-ROW1-PadP$57)") (class "Default")
      (node (ref "U3") (pin "P$57") (pinfunction "ROW1_P$57") (pintype "output"))
    )
    (net (code "109") (name "unconnected-(U3-ROW2-PadP$56)") (class "Default")
      (node (ref "U3") (pin "P$56") (pinfunction "ROW2_P$56") (pintype "output"))
    )
    (net (code "110") (name "unconnected-(U3-ROW3-PadP$55)") (class "Default")
      (node (ref "U3") (pin "P$55") (pinfunction "ROW3_P$55") (pintype "output"))
    )
    (net (code "111") (name "unconnected-(U3-SCL-PadP$39)") (class "Default")
      (node (ref "U3") (pin "P$39") (pinfunction "SCL_P$39") (pintype "output"))
    )
    (net (code "112") (name "unconnected-(U3-SDA-PadP$38)") (class "Default")
      (node (ref "U3") (pin "P$38") (pinfunction "SDA_P$38") (pintype "bidirectional"))
    )
    (net (code "113") (name "unconnected-(U3-SIM_PRE-PadP$33)") (class "Default")
      (node (ref "U3") (pin "P$33") (pinfunction "SIM_PRE_P$33") (pintype "input"))
    )
    (net (code "114") (name "unconnected-(U3-SPK1N-PadP$22)") (class "Default")
      (node (ref "U3") (pin "P$22") (pinfunction "SPK1N_P$22") (pintype "output"))
    )
    (net (code "115") (name "unconnected-(U3-SPK1P-PadP$21)") (class "Default")
      (node (ref "U3") (pin "P$21") (pinfunction "SPK1P_P$21") (pintype "output"))
    )
    (net (code "116") (name "unconnected-(U3-USB_DM-PadP$27)") (class "Default")
      (node (ref "U3") (pin "P$27") (pinfunction "USB_DM_P$27") (pintype "bidirectional"))
    )
    (net (code "117") (name "unconnected-(U3-USB_DP-PadP$26)") (class "Default")
      (node (ref "U3") (pin "P$26") (pinfunction "USB_DP_P$26") (pintype "bidirectional"))
    )
    (net (code "118") (name "unconnected-(X7-5-PadC6)") (class "Default")
      (node (ref "X7") (pin "C6") (pinfunction "5_C6") (pintype "passive"))
    )
  )
)
